# Channel_supply.net
KiCad netlist of a schematic drawn in Altium Designer
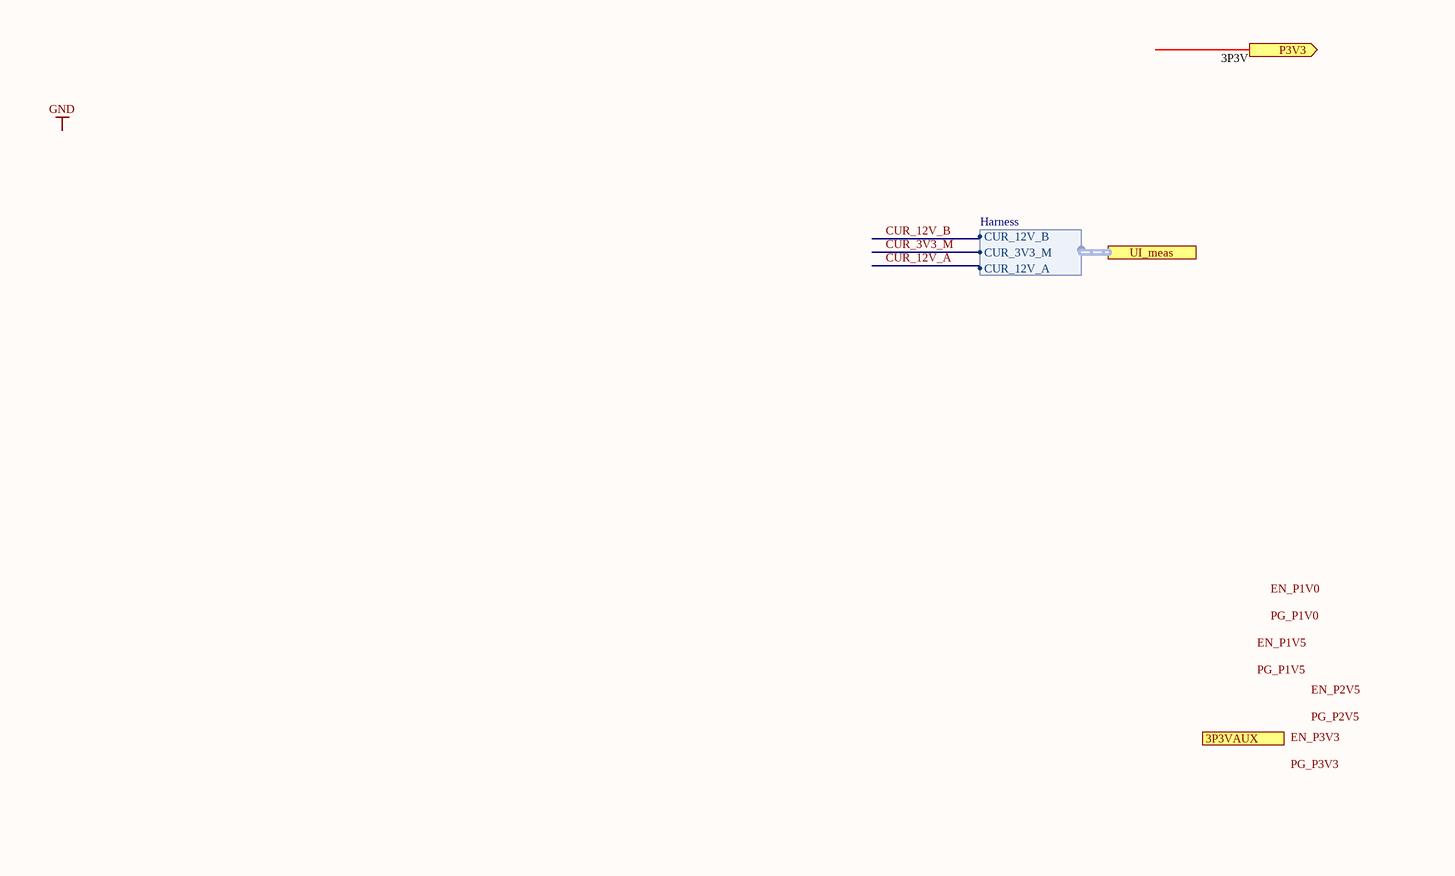
[diagram p0: Channel_supply.SchDoc, left]
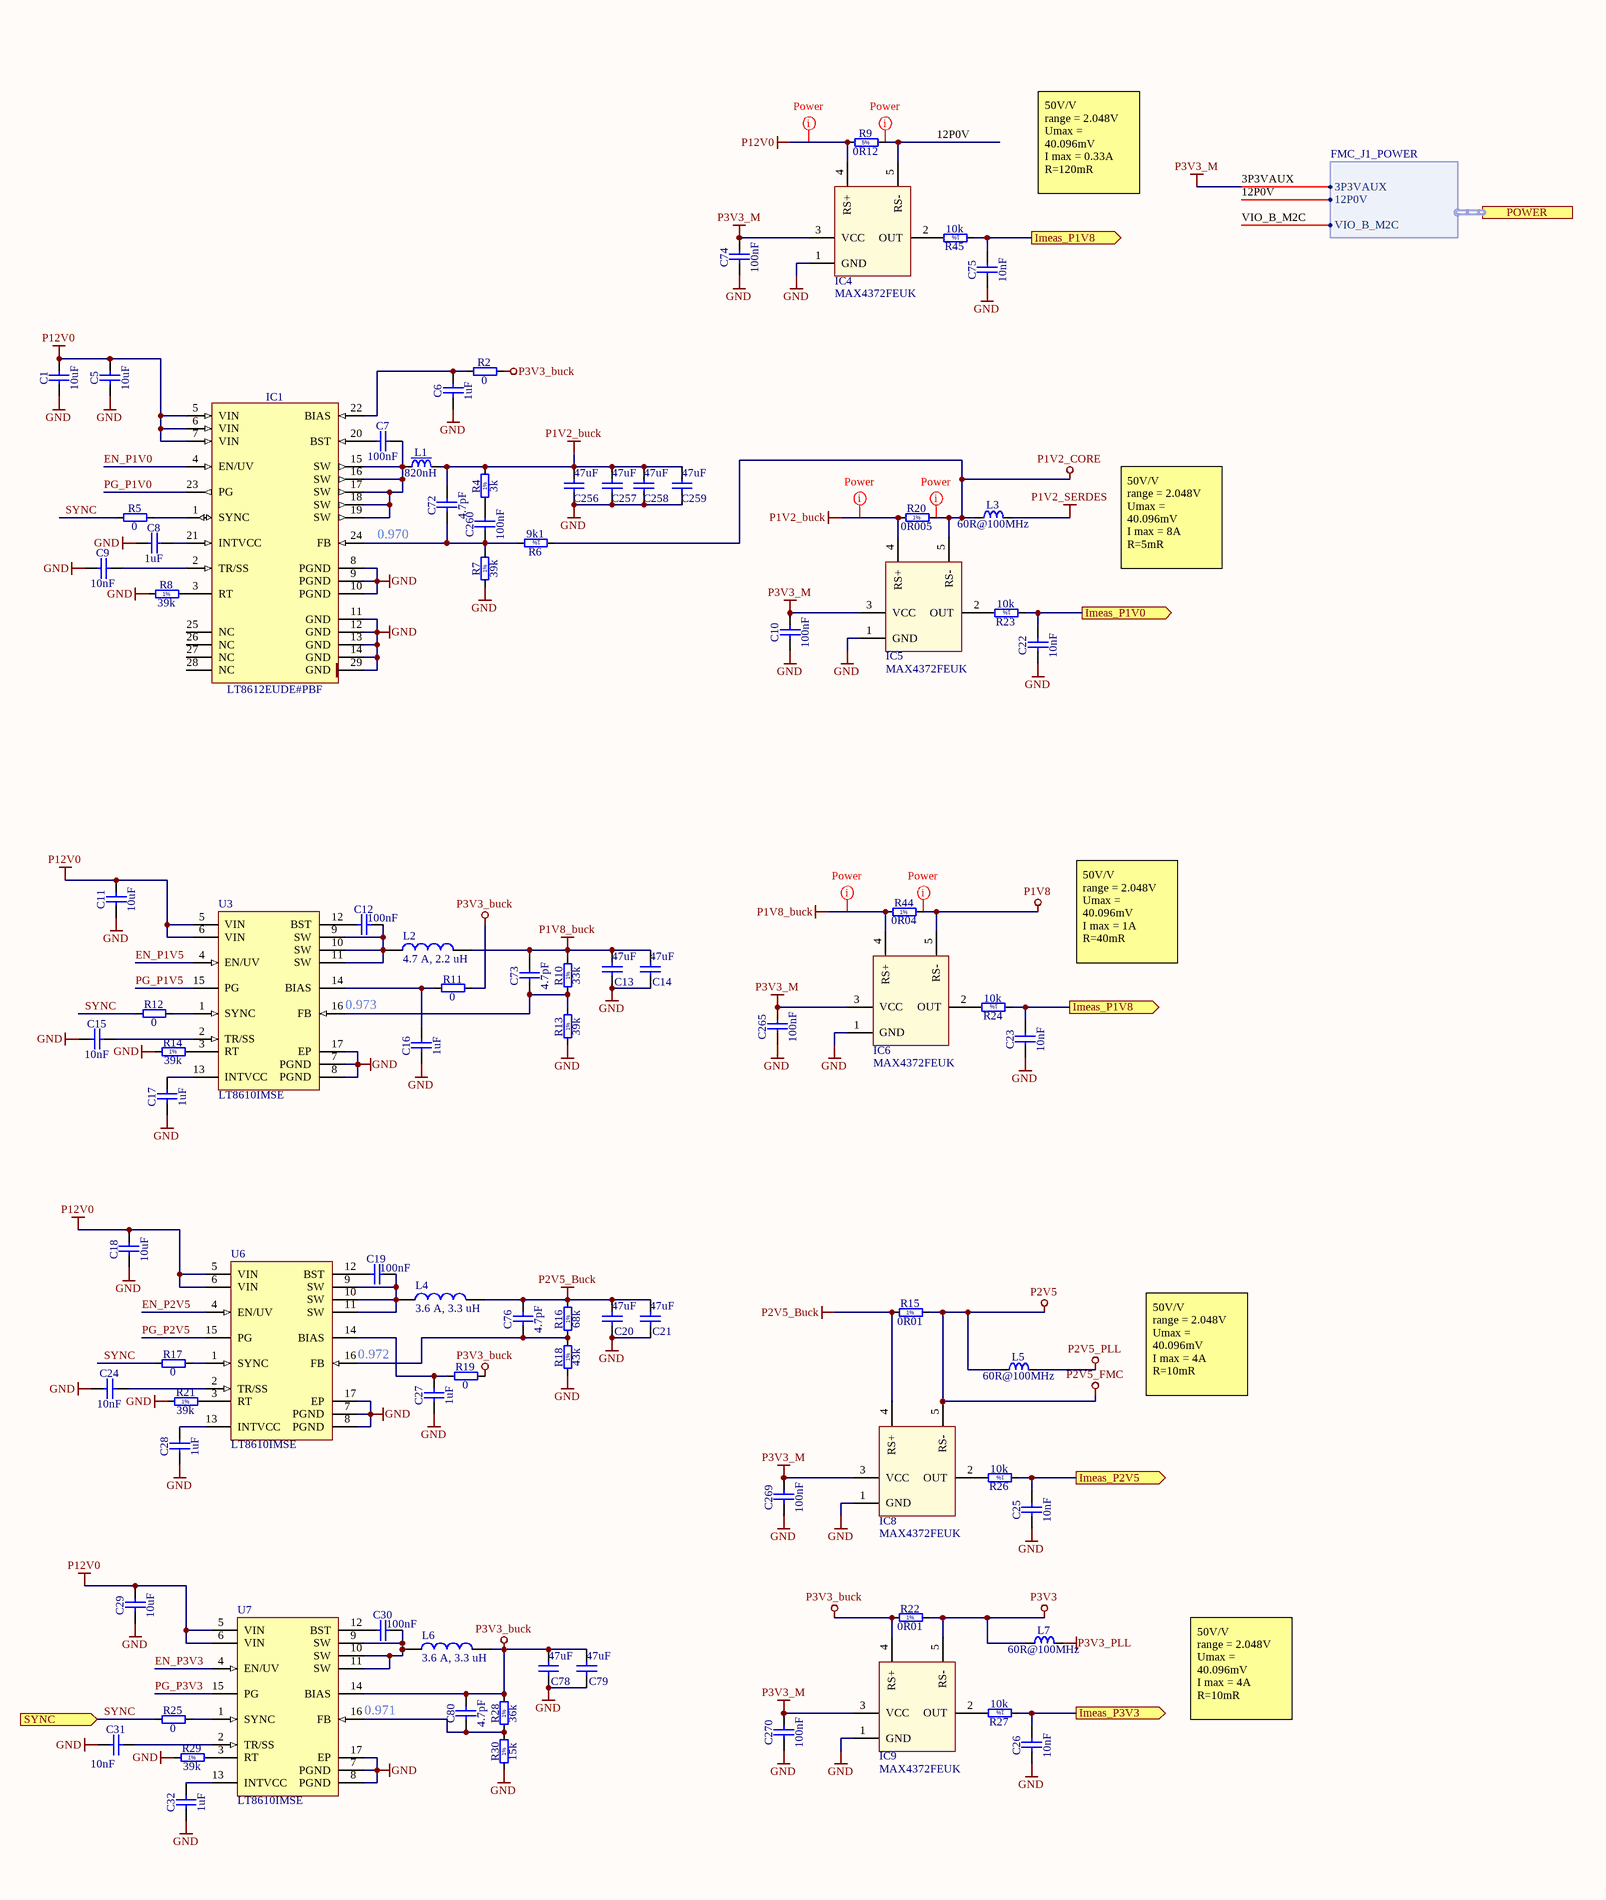
[diagram p1: Channel_supply.SchDoc, right]

(export (version "E")
  (design (tool "Eeschema 10.0.6"))
  (components
    (comp (ref "C1")
      (value "10uF")
      (footprint "CAPC2012X95N")
      (description "Non-polarised capacitor")
      (fields (field (name "PART NUMBER") "CC0805_10UF_25V_10%_X5R") (field (name "VOLTAGE") "25V"))
      (libsource (lib "Capacitors") (part "Capacitor - non polarized"))
    )
    (comp (ref "C5")
      (value "10uF")
      (footprint "CAPC2012X95N")
      (description "Non-polarised capacitor")
      (fields (field (name "PART NUMBER") "CC0805_10UF_25V_10%_X5R") (field (name "VOLTAGE") "25V"))
      (libsource (lib "Capacitors") (part "Capacitor - non polarized"))
    )
    (comp (ref "C6")
      (value "1uF")
      (footprint "CAPC1608X87N")
      (description "Non-polarised capacitor")
      (fields (field (name "PART NUMBER") "CC0603_1UF_25V_10%_X7R") (field (name "VOLTAGE") "25V"))
      (libsource (lib "Capacitors") (part "Capacitor - non polarized"))
    )
    (comp (ref "C7")
      (value "100nF")
      (footprint "CAPC1005X55N")
      (description "Non-polarised capacitor")
      (fields
        (field (name "PART NUMBER") "CC0402_100NF_25V_10%_X7R_YUDEN_TMK105B7104KVHF")
        (field (name "VOLTAGE") "25V")
      )
      (libsource (lib "Capacitors") (part "Capacitor - non polarized"))
    )
    (comp (ref "C8")
      (value "1uF")
      (footprint "CAPC1608X87N")
      (description "Non-polarised capacitor")
      (fields (field (name "PART NUMBER") "CC0603_1UF_25V_10%_X7R") (field (name "VOLTAGE") "25V"))
      (libsource (lib "Capacitors") (part "Capacitor - non polarized"))
    )
    (comp (ref "C9")
      (value "10nF")
      (footprint "CAPC1005X55N")
      (description "Non-polarised capacitor")
      (fields (field (name "PART NUMBER") "CC0402_10NF_25V_10%_X7R") (field (name "VOLTAGE") "25V"))
      (libsource (lib "Capacitors") (part "Capacitor - non polarized"))
    )
    (comp (ref "C10")
      (value "100nF")
      (footprint "CAPC1005X55N")
      (description "Non-polarised capacitor")
      (fields
        (field (name "PART NUMBER") "CC0402_100NF_25V_10%_X7R_YUDEN_TMK105B7104KVHF")
        (field (name "VOLTAGE") "25V")
      )
      (libsource (lib "Capacitors") (part "Capacitor - non polarized"))
    )
    (comp (ref "C11")
      (value "10uF")
      (footprint "CAPC2012X95N")
      (description "Non-polarised capacitor")
      (fields (field (name "PART NUMBER") "CC0805_10UF_25V_10%_X5R") (field (name "VOLTAGE") "25V"))
      (libsource (lib "Capacitors") (part "Capacitor - non polarized"))
    )
    (comp (ref "C12")
      (value "100nF")
      (footprint "CAPC1005X55N")
      (description "Non-polarised capacitor")
      (fields
        (field (name "PART NUMBER") "CC0402_100NF_25V_10%_X7R_YUDEN_TMK105B7104KVHF")
        (field (name "VOLTAGE") "25V")
      )
      (libsource (lib "Capacitors") (part "Capacitor - non polarized"))
    )
    (comp (ref "C13")
      (value "47uF")
      (footprint "CAPC2012X140N")
      (description "Non-polarised capacitor")
      (fields (field (name "PART NUMBER") "CC0805_47UF_6.3V_20%_X5R") (field (name "MANUFACTURER") "GENERIC"))
      (libsource (lib "Capacitors") (part "Capacitor - non polarized"))
    )
    (comp (ref "C14")
      (value "47uF")
      (footprint "CAPC2012X140N")
      (description "Non-polarised capacitor")
      (fields (field (name "PART NUMBER") "CC0805_47UF_6.3V_20%_X5R") (field (name "MANUFACTURER") "GENERIC"))
      (libsource (lib "Capacitors") (part "Capacitor - non polarized"))
    )
    (comp (ref "C15")
      (value "10nF")
      (footprint "CAPC1005X55N")
      (description "Non-polarised capacitor")
      (fields (field (name "PART NUMBER") "CC0402_10NF_25V_10%_X7R") (field (name "VOLTAGE") "25V"))
      (libsource (lib "Capacitors") (part "Capacitor - non polarized"))
    )
    (comp (ref "C16")
      (value "1uF")
      (footprint "CAPC1608X87N")
      (description "Non-polarised capacitor")
      (fields (field (name "PART NUMBER") "CC0603_1UF_25V_10%_X7R") (field (name "VOLTAGE") "25V"))
      (libsource (lib "Capacitors") (part "Capacitor - non polarized"))
    )
    (comp (ref "C17")
      (value "1uF")
      (footprint "CAPC1608X87N")
      (description "Non-polarised capacitor")
      (fields (field (name "PART NUMBER") "CC0603_1UF_25V_10%_X7R") (field (name "VOLTAGE") "25V"))
      (libsource (lib "Capacitors") (part "Capacitor - non polarized"))
    )
    (comp (ref "C18")
      (value "10uF")
      (footprint "CAPC2012X95N")
      (description "Non-polarised capacitor")
      (fields (field (name "PART NUMBER") "CC0805_10UF_25V_10%_X5R") (field (name "VOLTAGE") "25V"))
      (libsource (lib "Capacitors") (part "Capacitor - non polarized"))
    )
    (comp (ref "C19")
      (value "100nF")
      (footprint "CAPC1005X55N")
      (description "Non-polarised capacitor")
      (fields
        (field (name "PART NUMBER") "CC0402_100NF_25V_10%_X7R_YUDEN_TMK105B7104KVHF")
        (field (name "VOLTAGE") "25V")
      )
      (libsource (lib "Capacitors") (part "Capacitor - non polarized"))
    )
    (comp (ref "C20")
      (value "47uF")
      (footprint "CAPC2012X140N")
      (description "Non-polarised capacitor")
      (fields (field (name "PART NUMBER") "CC0805_47UF_6.3V_20%_X5R") (field (name "MANUFACTURER") "GENERIC"))
      (libsource (lib "Capacitors") (part "Capacitor - non polarized"))
    )
    (comp (ref "C21")
      (value "47uF")
      (footprint "CAPC2012X140N")
      (description "Non-polarised capacitor")
      (fields (field (name "PART NUMBER") "CC0805_47UF_6.3V_20%_X5R") (field (name "MANUFACTURER") "GENERIC"))
      (libsource (lib "Capacitors") (part "Capacitor - non polarized"))
    )
    (comp (ref "C22")
      (value "10nF")
      (footprint "CAPC1005X55N")
      (description "Non-polarised capacitor")
      (fields (field (name "PART NUMBER") "CC0402_10NF_50V_10%_X7R") (field (name "VOLTAGE") "50V"))
      (libsource (lib "Capacitors") (part "Capacitor - non polarized"))
    )
    (comp (ref "C23")
      (value "10nF")
      (footprint "CAPC1005X55N")
      (description "Non-polarised capacitor")
      (fields (field (name "PART NUMBER") "CC0402_10NF_50V_10%_X7R") (field (name "VOLTAGE") "50V"))
      (libsource (lib "Capacitors") (part "Capacitor - non polarized"))
    )
    (comp (ref "C24")
      (value "10nF")
      (footprint "CAPC1005X55N")
      (description "Non-polarised capacitor")
      (fields (field (name "PART NUMBER") "CC0402_10NF_25V_10%_X7R") (field (name "VOLTAGE") "25V"))
      (libsource (lib "Capacitors") (part "Capacitor - non polarized"))
    )
    (comp (ref "C25")
      (value "10nF")
      (footprint "CAPC1005X55N")
      (description "Non-polarised capacitor")
      (fields (field (name "PART NUMBER") "CC0402_10NF_50V_10%_X7R") (field (name "VOLTAGE") "50V"))
      (libsource (lib "Capacitors") (part "Capacitor - non polarized"))
    )
    (comp (ref "C26")
      (value "10nF")
      (footprint "CAPC1005X55N")
      (description "Non-polarised capacitor")
      (fields (field (name "PART NUMBER") "CC0402_10NF_50V_10%_X7R") (field (name "VOLTAGE") "50V"))
      (libsource (lib "Capacitors") (part "Capacitor - non polarized"))
    )
    (comp (ref "C27")
      (value "1uF")
      (footprint "CAPC1608X87N")
      (description "Non-polarised capacitor")
      (fields (field (name "PART NUMBER") "CC0603_1UF_25V_10%_X7R") (field (name "VOLTAGE") "25V"))
      (libsource (lib "Capacitors") (part "Capacitor - non polarized"))
    )
    (comp (ref "C28")
      (value "1uF")
      (footprint "CAPC1608X87N")
      (description "Non-polarised capacitor")
      (fields (field (name "PART NUMBER") "CC0603_1UF_25V_10%_X7R") (field (name "VOLTAGE") "25V"))
      (libsource (lib "Capacitors") (part "Capacitor - non polarized"))
    )
    (comp (ref "C29")
      (value "10uF")
      (footprint "CAPC2012X95N")
      (description "Non-polarised capacitor")
      (fields (field (name "PART NUMBER") "CC0805_10UF_25V_10%_X5R") (field (name "VOLTAGE") "25V"))
      (libsource (lib "Capacitors") (part "Capacitor - non polarized"))
    )
    (comp (ref "C30")
      (value "100nF")
      (footprint "CAPC1005X55N")
      (description "Non-polarised capacitor")
      (fields
        (field (name "PART NUMBER") "CC0402_100NF_25V_10%_X7R_YUDEN_TMK105B7104KVHF")
        (field (name "VOLTAGE") "25V")
      )
      (libsource (lib "Capacitors") (part "Capacitor - non polarized"))
    )
    (comp (ref "C31")
      (value "10nF")
      (footprint "CAPC1005X55N")
      (description "Non-polarised capacitor")
      (fields (field (name "PART NUMBER") "CC0402_10NF_25V_10%_X7R") (field (name "VOLTAGE") "25V"))
      (libsource (lib "Capacitors") (part "Capacitor - non polarized"))
    )
    (comp (ref "C32")
      (value "1uF")
      (footprint "CAPC1608X87N")
      (description "Non-polarised capacitor")
      (fields (field (name "PART NUMBER") "CC0603_1UF_25V_10%_X7R") (field (name "VOLTAGE") "25V"))
      (libsource (lib "Capacitors") (part "Capacitor - non polarized"))
    )
    (comp (ref "C72")
      (value "4.7pF")
      (footprint "CAPC1005X55N")
      (description "Non-polarised capacitor")
      (fields (field (name "PART NUMBER") "CC0402_4.7PF_50V_0.25PF_C0G") (field (name "VOLTAGE") "50V"))
      (libsource (lib "Capacitors") (part "Capacitor - non polarized"))
    )
    (comp (ref "C73")
      (value "4.7pF")
      (footprint "CAPC1005X55N")
      (description "Non-polarised capacitor")
      (fields (field (name "PART NUMBER") "CC0402_4.7PF_50V_0.25PF_C0G") (field (name "VOLTAGE") "50V"))
      (libsource (lib "Capacitors") (part "Capacitor - non polarized"))
    )
    (comp (ref "C74")
      (value "100nF")
      (footprint "CAPC1005X55N")
      (description "Non-polarised capacitor")
      (fields
        (field (name "PART NUMBER") "CC0402_100NF_25V_10%_X7R_YUDEN_TMK105B7104KVHF")
        (field (name "VOLTAGE") "25V")
      )
      (libsource (lib "Capacitors") (part "Capacitor - non polarized"))
    )
    (comp (ref "C75")
      (value "10nF")
      (footprint "CAPC1005X55N")
      (description "Non-polarised capacitor")
      (fields (field (name "PART NUMBER") "CC0402_10NF_50V_10%_X7R") (field (name "VOLTAGE") "50V"))
      (libsource (lib "Capacitors") (part "Capacitor - non polarized"))
    )
    (comp (ref "C76")
      (value "4.7pF")
      (footprint "CAPC1005X55N")
      (description "Non-polarised capacitor")
      (fields (field (name "PART NUMBER") "CC0402_4.7PF_50V_0.25PF_C0G") (field (name "VOLTAGE") "50V"))
      (libsource (lib "Capacitors") (part "Capacitor - non polarized"))
    )
    (comp (ref "C78")
      (value "47uF")
      (footprint "CAPC2012X140N")
      (description "Non-polarised capacitor")
      (fields (field (name "PART NUMBER") "CC0805_47UF_6.3V_20%_X5R") (field (name "MANUFACTURER") "GENERIC"))
      (libsource (lib "Capacitors") (part "Capacitor - non polarized"))
    )
    (comp (ref "C79")
      (value "47uF")
      (footprint "CAPC2012X140N")
      (description "Non-polarised capacitor")
      (fields (field (name "PART NUMBER") "CC0805_47UF_6.3V_20%_X5R") (field (name "MANUFACTURER") "GENERIC"))
      (libsource (lib "Capacitors") (part "Capacitor - non polarized"))
    )
    (comp (ref "C80")
      (value "4.7pF")
      (footprint "CAPC1005X55N")
      (description "Non-polarised capacitor")
      (fields (field (name "PART NUMBER") "CC0402_4.7PF_50V_0.25PF_C0G") (field (name "VOLTAGE") "50V"))
      (libsource (lib "Capacitors") (part "Capacitor - non polarized"))
    )
    (comp (ref "C256")
      (value "47uF")
      (footprint "CAPC2012X140N")
      (description "Non-polarised capacitor")
      (fields (field (name "PART NUMBER") "CC0805_47UF_6.3V_20%_X5R") (field (name "MANUFACTURER") "GENERIC"))
      (libsource (lib "Capacitors") (part "Capacitor - non polarized"))
    )
    (comp (ref "C257")
      (value "47uF")
      (footprint "CAPC2012X140N")
      (description "Non-polarised capacitor")
      (fields (field (name "PART NUMBER") "CC0805_47UF_6.3V_20%_X5R") (field (name "MANUFACTURER") "GENERIC"))
      (libsource (lib "Capacitors") (part "Capacitor - non polarized"))
    )
    (comp (ref "C258")
      (value "47uF")
      (footprint "CAPC2012X140N")
      (description "Non-polarised capacitor")
      (fields (field (name "PART NUMBER") "CC0805_47UF_6.3V_20%_X5R") (field (name "MANUFACTURER") "GENERIC"))
      (libsource (lib "Capacitors") (part "Capacitor - non polarized"))
    )
    (comp (ref "C259")
      (value "47uF")
      (footprint "CAPC2012X140N")
      (description "Non-polarised capacitor")
      (fields (field (name "PART NUMBER") "CC0805_47UF_6.3V_20%_X5R") (field (name "MANUFACTURER") "GENERIC"))
      (libsource (lib "Capacitors") (part "Capacitor - non polarized"))
    )
    (comp (ref "C260")
      (value "100nF")
      (footprint "CAPC1005X55N")
      (description "Non-polarised capacitor")
      (fields
        (field (name "PART NUMBER") "CC0402_100NF_25V_10%_X7R_YUDEN_TMK105B7104KVHF")
        (field (name "VOLTAGE") "25V")
      )
      (libsource (lib "Capacitors") (part "Capacitor - non polarized"))
    )
    (comp (ref "C265")
      (value "100nF")
      (footprint "CAPC1005X55N")
      (description "Non-polarised capacitor")
      (fields
        (field (name "PART NUMBER") "CC0402_100NF_25V_10%_X7R_YUDEN_TMK105B7104KVHF")
        (field (name "VOLTAGE") "25V")
      )
      (libsource (lib "Capacitors") (part "Capacitor - non polarized"))
    )
    (comp (ref "C269")
      (value "100nF")
      (footprint "CAPC1005X55N")
      (description "Non-polarised capacitor")
      (fields
        (field (name "PART NUMBER") "CC0402_100NF_25V_10%_X7R_YUDEN_TMK105B7104KVHF")
        (field (name "VOLTAGE") "25V")
      )
      (libsource (lib "Capacitors") (part "Capacitor - non polarized"))
    )
    (comp (ref "C270")
      (value "100nF")
      (footprint "CAPC1005X55N")
      (description "Non-polarised capacitor")
      (fields
        (field (name "PART NUMBER") "CC0402_100NF_25V_10%_X7R_YUDEN_TMK105B7104KVHF")
        (field (name "VOLTAGE") "25V")
      )
      (libsource (lib "Capacitors") (part "Capacitor - non polarized"))
    )
    (comp (ref "IC1")
      (value "LT8612EUDE#PBF")
      (footprint "QFN50P300X600X80-29N-R180X485")
      (description "42V, 6A Synchronous Step-Down Regulator with 3µA Quiescent Current")
      (fields (field (name "MANUFACTURER") "LINEAR TECHNOLOGY"))
      (libsource (lib "ICs And Semiconductors") (part "LT8612"))
    )
    (comp (ref "IC4")
      (value "MAX4372FEUK")
      (footprint "SOT95P270X145-5N")
      (fields (field (name "MANUFACTURER") "Maxim"))
      (libsource (lib "LIBRARY_SCH") (part "PM_MAX4372FEUK"))
    )
    (comp (ref "IC5")
      (value "MAX4372FEUK")
      (footprint "SOT95P270X145-5N")
      (fields (field (name "MANUFACTURER") "Maxim"))
      (libsource (lib "LIBRARY_SCH") (part "PM_MAX4372FEUK"))
    )
    (comp (ref "IC6")
      (value "MAX4372FEUK")
      (footprint "SOT95P270X145-5N")
      (fields (field (name "MANUFACTURER") "Maxim"))
      (libsource (lib "LIBRARY_SCH") (part "PM_MAX4372FEUK"))
    )
    (comp (ref "IC8")
      (value "MAX4372FEUK")
      (footprint "SOT95P270X145-5N")
      (fields (field (name "MANUFACTURER") "Maxim"))
      (libsource (lib "LIBRARY_SCH") (part "PM_MAX4372FEUK"))
    )
    (comp (ref "IC9")
      (value "MAX4372FEUK")
      (footprint "SOT95P270X145-5N")
      (fields (field (name "MANUFACTURER") "Maxim"))
      (libsource (lib "LIBRARY_SCH") (part "PM_MAX4372FEUK"))
    )
    (comp (ref "L1")
      (value "820nH")
      (footprint "INDP4040X21N")
      (description "Inductor With Core")
      (fields (field (name "PART NUMBER") "IND_820NH_COILCRAFT_XEL4020-821MEC") (field (name "POWER") "10A"))
      (libsource (lib "LIBRARY_SCH") (part "L_POWER_XEL4020_820uH_10A"))
    )
    (comp (ref "L2")
      (value "4.7 A, 2.2 uH")
      (footprint "WE-MAIA_4020")
      (description "WE-MAIA SMD Power Inductor, size 4020, 4.7 A, 2.2 uH")
      (fields (field (name "PART NUMBER") "78438356022"))
      (libsource (lib "ALTIUM-WE-MAIA-rev17b") (part "78438356022"))
    )
    (comp (ref "L3")
      (value "60R@100MHz")
      (footprint "INDC4516X180N")
      (description "Inductor")
      (fields (field (name "PART NUMBER") "IND1806_MURATA_BLM41PG600SN1L") (field (name "POWER") "6A"))
      (libsource (lib "Inductors & Transformers") (part "Inductor"))
    )
    (comp (ref "L4")
      (value "3.6 A, 3.3 uH")
      (footprint "WE-MAIA_4020")
      (description "WE-MAIA SMD Power Inductor, size 4020, 3.6 A, 3.3 uH")
      (fields (field (name "PART NUMBER") "78438356033"))
      (libsource (lib "ALTIUM-WE-MAIA-rev17b") (part "78438356033"))
    )
    (comp (ref "L5")
      (value "60R@100MHz")
      (footprint "INDC4516X180N")
      (description "Inductor")
      (fields (field (name "PART NUMBER") "IND1806_MURATA_BLM41PG600SN1L") (field (name "POWER") "6A"))
      (libsource (lib "Inductors & Transformers") (part "Inductor"))
    )
    (comp (ref "L6")
      (value "3.6 A, 3.3 uH")
      (footprint "WE-MAIA_4020")
      (description "WE-MAIA SMD Power Inductor, size 4020, 3.6 A, 3.3 uH")
      (fields (field (name "PART NUMBER") "78438356033"))
      (libsource (lib "ALTIUM-WE-MAIA-rev17b") (part "78438356033"))
    )
    (comp (ref "L7")
      (value "60R@100MHz")
      (footprint "INDC4516X180N")
      (description "Inductor")
      (fields (field (name "PART NUMBER") "IND1806_MURATA_BLM41PG600SN1L") (field (name "POWER") "6A"))
      (libsource (lib "Inductors & Transformers") (part "Inductor"))
    )
    (comp (ref "R2")
      (value "0")
      (footprint "RESC1005X40N")
      (description "Resistor")
      (fields (field (name "PART NUMBER") "R0402_0R_JUMPER") (field (name "MANUFACTURER") "GENERIC"))
      (libsource (lib "Resistors") (part "Resistor"))
    )
    (comp (ref "R4")
      (value "3k")
      (footprint "RESC1005X40N")
      (description "Resistor - 1%")
      (fields (field (name "PART NUMBER") "R0402_3K_1%_0.0625W_100PPM") (field (name "POWER") "0.0625W"))
      (libsource (lib "Resistors") (part "Resistor - 1%"))
    )
    (comp (ref "R5")
      (value "0")
      (footprint "RESC1005X40N")
      (description "Resistor")
      (fields (field (name "PART NUMBER") "R0402_0R_JUMPER") (field (name "MANUFACTURER") "GENERIC"))
      (libsource (lib "Resistors") (part "Resistor"))
    )
    (comp (ref "R6")
      (value "9k1")
      (footprint "RESC1005X40N")
      (description "Resistor - 1%")
      (fields (field (name "PART NUMBER") "R0402_9K1_1%_0.0625W_100PPM") (field (name "POWER") "0.0625W"))
      (libsource (lib "Resistors") (part "Resistor - 1%"))
    )
    (comp (ref "R7")
      (value "39k")
      (footprint "RESC1005X40N")
      (description "Resistor - 1%")
      (fields (field (name "PART NUMBER") "R0402_39K_1%_0.0625W_100PPM") (field (name "POWER") "0.0625W"))
      (libsource (lib "Resistors") (part "Resistor - 1%"))
    )
    (comp (ref "R8")
      (value "39k")
      (footprint "RESC1005X40N")
      (description "Resistor - 1%")
      (fields (field (name "PART NUMBER") "R0402_39K_1%_0.0625W_100PPM") (field (name "POWER") "0.0625W"))
      (libsource (lib "Resistors") (part "Resistor - 1%"))
    )
    (comp (ref "R9")
      (value "0R12")
      (footprint "RESC2012X70N")
      (description "Resistor - 5%")
      (fields
        (field (name "PART NUMBER") "R0805_0R12_5%_0.25W_250PPM_PANASONIC_ERJ")
        (field (name "POWER") "0.25W")
      )
      (libsource (lib "Resistors") (part "Resistor - 5%"))
    )
    (comp (ref "R10")
      (value "33k")
      (footprint "RESC1005X40N")
      (description "Resistor - 1%")
      (fields (field (name "PART NUMBER") "R0402_33K_1%_0.0625W_100PPM") (field (name "POWER") "0.0625W"))
      (libsource (lib "Resistors") (part "Resistor - 1%"))
    )
    (comp (ref "R11")
      (value "0")
      (footprint "RESC1005X40N")
      (description "Resistor")
      (fields (field (name "PART NUMBER") "R0402_0R_JUMPER") (field (name "MANUFACTURER") "GENERIC"))
      (libsource (lib "Resistors") (part "Resistor"))
    )
    (comp (ref "R12")
      (value "0")
      (footprint "RESC1005X40N")
      (description "Resistor")
      (fields (field (name "PART NUMBER") "R0402_0R_JUMPER") (field (name "MANUFACTURER") "GENERIC"))
      (libsource (lib "Resistors") (part "Resistor"))
    )
    (comp (ref "R13")
      (value "39k")
      (footprint "RESC1005X40N")
      (description "Resistor - 1%")
      (fields (field (name "PART NUMBER") "R0402_39K_1%_0.0625W_100PPM") (field (name "POWER") "0.0625W"))
      (libsource (lib "Resistors") (part "Resistor - 1%"))
    )
    (comp (ref "R14")
      (value "39k")
      (footprint "RESC1005X40N")
      (description "Resistor - 1%")
      (fields (field (name "PART NUMBER") "R0402_39K_1%_0.0625W_100PPM") (field (name "POWER") "0.0625W"))
      (libsource (lib "Resistors") (part "Resistor - 1%"))
    )
    (comp (ref "R15")
      (value "0R01")
      (footprint "RESC3216X80N")
      (description "Resistor - 1%")
      (fields (field (name "PART NUMBER") "R1206_0R01_1%_1W_100PPM_TT_LRMAM1206") (field (name "POWER") "1W"))
      (libsource (lib "Resistors") (part "Resistor - 1%"))
    )
    (comp (ref "R16")
      (value "68k")
      (footprint "RESC1005X40N")
      (description "Resistor - 1%")
      (fields (field (name "PART NUMBER") "R0402_68K_1%_0.0625W_100PPM") (field (name "POWER") "0.0625W"))
      (libsource (lib "Resistors") (part "Resistor - 1%"))
    )
    (comp (ref "R17")
      (value "0")
      (footprint "RESC1005X40N")
      (description "Resistor")
      (fields (field (name "PART NUMBER") "R0402_0R_JUMPER") (field (name "MANUFACTURER") "GENERIC"))
      (libsource (lib "Resistors") (part "Resistor"))
    )
    (comp (ref "R18")
      (value "43k")
      (footprint "RESC1005X40N")
      (description "Resistor - 1%")
      (fields (field (name "PART NUMBER") "R0402_43K_1%_0.0625W_100PPM") (field (name "POWER") "0.0625W"))
      (libsource (lib "Resistors") (part "Resistor - 1%"))
    )
    (comp (ref "R19")
      (value "0")
      (footprint "RESC1005X40N")
      (description "Resistor")
      (fields (field (name "PART NUMBER") "R0402_0R_JUMPER") (field (name "MANUFACTURER") "GENERIC"))
      (libsource (lib "Resistors") (part "Resistor"))
    )
    (comp (ref "R20")
      (value "0R005")
      (footprint "RESC3216X80N")
      (description "Resistor - 1%")
      (fields
        (field (name "PART NUMBER") "R1206_0R005_1%_1W_100PPM_TT_LRMAM1206")
        (field (name "POWER") "1W")
      )
      (libsource (lib "Resistors") (part "Resistor - 1%"))
    )
    (comp (ref "R21")
      (value "39k")
      (footprint "RESC1005X40N")
      (description "Resistor - 1%")
      (fields (field (name "PART NUMBER") "R0402_39K_1%_0.0625W_100PPM") (field (name "POWER") "0.0625W"))
      (libsource (lib "Resistors") (part "Resistor - 1%"))
    )
    (comp (ref "R22")
      (value "0R01")
      (footprint "RESC3216X80N")
      (description "Resistor - 1%")
      (fields (field (name "PART NUMBER") "R1206_0R01_1%_1W_100PPM_TT_LRMAM1206") (field (name "POWER") "1W"))
      (libsource (lib "Resistors") (part "Resistor - 1%"))
    )
    (comp (ref "R23")
      (value "10k")
      (footprint "RESC1005X40N")
      (description "Resistor - 1%")
      (fields (field (name "PART NUMBER") "R0402_10K_1%_0.0625W_100PPM") (field (name "POWER") "0.0625W"))
      (libsource (lib "Resistors") (part "Resistor - 1%"))
    )
    (comp (ref "R24")
      (value "10k")
      (footprint "RESC1005X40N")
      (description "Resistor - 1%")
      (fields (field (name "PART NUMBER") "R0402_10K_1%_0.0625W_100PPM") (field (name "POWER") "0.0625W"))
      (libsource (lib "Resistors") (part "Resistor - 1%"))
    )
    (comp (ref "R25")
      (value "0")
      (footprint "RESC1005X40N")
      (description "Resistor")
      (fields (field (name "PART NUMBER") "R0402_0R_JUMPER") (field (name "MANUFACTURER") "GENERIC"))
      (libsource (lib "Resistors") (part "Resistor"))
    )
    (comp (ref "R26")
      (value "10k")
      (footprint "RESC1005X40N")
      (description "Resistor - 1%")
      (fields (field (name "PART NUMBER") "R0402_10K_1%_0.0625W_100PPM") (field (name "POWER") "0.0625W"))
      (libsource (lib "Resistors") (part "Resistor - 1%"))
    )
    (comp (ref "R27")
      (value "10k")
      (footprint "RESC1005X40N")
      (description "Resistor - 1%")
      (fields (field (name "PART NUMBER") "R0402_10K_1%_0.0625W_100PPM") (field (name "POWER") "0.0625W"))
      (libsource (lib "Resistors") (part "Resistor - 1%"))
    )
    (comp (ref "R28")
      (value "36k")
      (footprint "RESC1005X40N")
      (description "Resistor - 1%")
      (fields (field (name "PART NUMBER") "R0402_36K_1%_0.0625W_100PPM") (field (name "POWER") "0.0625W"))
      (libsource (lib "Resistors") (part "Resistor - 1%"))
    )
    (comp (ref "R29")
      (value "39k")
      (footprint "RESC1005X40N")
      (description "Resistor - 1%")
      (fields (field (name "PART NUMBER") "R0402_39K_1%_0.0625W_100PPM") (field (name "POWER") "0.0625W"))
      (libsource (lib "Resistors") (part "Resistor - 1%"))
    )
    (comp (ref "R30")
      (value "15k")
      (footprint "RESC1005X40N")
      (description "Resistor - 1%")
      (fields (field (name "PART NUMBER") "R0402_15K_1%_0.0625W_100PPM") (field (name "POWER") "0.0625W"))
      (libsource (lib "Resistors") (part "Resistor - 1%"))
    )
    (comp (ref "R44")
      (value "0R04")
      (footprint "RESC3216X89N")
      (description "Resistor - 1%")
      (fields
        (field (name "PART NUMBER") "R1206_0R04_1%_0.5W_100PPM_VISHAY_WSL")
        (field (name "POWER") "0.5W")
      )
      (libsource (lib "Resistors") (part "Resistor - 1%"))
    )
    (comp (ref "R45")
      (value "10k")
      (footprint "RESC1005X40N")
      (description "Resistor - 1%")
      (fields (field (name "PART NUMBER") "R0402_10K_1%_0.0625W_100PPM") (field (name "POWER") "0.0625W"))
      (libsource (lib "Resistors") (part "Resistor - 1%"))
    )
    (comp (ref "U3")
      (value "LT8610IMSE")
      (footprint "LT-MSE-16-EDP_L")
      (fields (field (name "MANUFACTURER") "Linear Technology"))
      (libsource (lib "Altium Content Vault") (part "LT-LT8610-MSE-16"))
    )
    (comp (ref "U6")
      (value "LT8610IMSE")
      (footprint "LT-MSE-16-EDP_L")
      (fields (field (name "MANUFACTURER") "Linear Technology"))
      (libsource (lib "Altium Content Vault") (part "LT-LT8610-MSE-16"))
    )
    (comp (ref "U7")
      (value "LT8610IMSE")
      (footprint "LT-MSE-16-EDP_L")
      (fields (field (name "MANUFACTURER") "Linear Technology"))
      (libsource (lib "Altium Content Vault") (part "LT-LT8610-MSE-16"))
    )
  )
  (nets
    (net (code "3") (name "/12P0V") (class "Default")
      (node (ref "IC4") (pin "5") (pinfunction "RS-_5") (pintype "passive"))
      (node (ref "R9") (pin "2") (pinfunction "2_2") (pintype "passive"))
    )
    (net (code "7") (name "/EN_P1V0") (class "Default")
      (node (ref "IC1") (pin "4") (pinfunction "EN/UV_4") (pintype "input"))
    )
    (net (code "8") (name "/EN_P1V5") (class "Default")
      (node (ref "U3") (pin "4") (pinfunction "EN/UV_4") (pintype "input"))
    )
    (net (code "9") (name "/EN_P2V5") (class "Default")
      (node (ref "U6") (pin "4") (pinfunction "EN/UV_4") (pintype "input"))
    )
    (net (code "10") (name "/EN_P3V3") (class "Default")
      (node (ref "U7") (pin "4") (pinfunction "EN/UV_4") (pintype "input"))
    )
    (net (code "11") (name "/Imeas_P1V0") (class "Default")
      (node (ref "C22") (pin "2") (pinfunction "2_2") (pintype "passive"))
      (node (ref "R23") (pin "1") (pinfunction "1_1") (pintype "passive"))
    )
    (net (code "12") (name "/Imeas_P1V8") (class "Default")
      (node (ref "C23") (pin "2") (pinfunction "2_2") (pintype "passive"))
      (node (ref "C75") (pin "2") (pinfunction "2_2") (pintype "passive"))
      (node (ref "R24") (pin "1") (pinfunction "1_1") (pintype "passive"))
      (node (ref "R45") (pin "1") (pinfunction "1_1") (pintype "passive"))
    )
    (net (code "13") (name "/Imeas_P2V5") (class "Default")
      (node (ref "C25") (pin "2") (pinfunction "2_2") (pintype "passive"))
      (node (ref "R26") (pin "1") (pinfunction "1_1") (pintype "passive"))
    )
    (net (code "14") (name "/Imeas_P3V3") (class "Default")
      (node (ref "C26") (pin "2") (pinfunction "2_2") (pintype "passive"))
      (node (ref "R27") (pin "1") (pinfunction "1_1") (pintype "passive"))
    )
    (net (code "15") (name "/PG_P1V0") (class "Default")
      (node (ref "IC1") (pin "23") (pinfunction "PG_23") (pintype "output"))
    )
    (net (code "16") (name "/PG_P1V5") (class "Default")
      (node (ref "U3") (pin "15") (pinfunction "PG_15") (pintype "tri_state"))
    )
    (net (code "17") (name "/PG_P2V5") (class "Default")
      (node (ref "U6") (pin "15") (pinfunction "PG_15") (pintype "tri_state"))
    )
    (net (code "18") (name "/PG_P3V3") (class "Default")
      (node (ref "U7") (pin "15") (pinfunction "PG_15") (pintype "tri_state"))
    )
    (net (code "19") (name "/SYNC") (class "Default")
      (node (ref "R12") (pin "1") (pinfunction "1_1") (pintype "passive"))
      (node (ref "R17") (pin "1") (pinfunction "1_1") (pintype "passive"))
      (node (ref "R25") (pin "1") (pinfunction "1_1") (pintype "passive"))
      (node (ref "R5") (pin "1") (pinfunction "1_1") (pintype "passive"))
    )
    (net (code "23") (name "GND") (class "Default")
      (node (ref "C1") (pin "1") (pinfunction "1_1") (pintype "passive"))
      (node (ref "C10") (pin "1") (pinfunction "1_1") (pintype "passive"))
      (node (ref "C11") (pin "1") (pinfunction "1_1") (pintype "passive"))
      (node (ref "C13") (pin "1") (pinfunction "1_1") (pintype "passive"))
      (node (ref "C14") (pin "1") (pinfunction "1_1") (pintype "passive"))
      (node (ref "C15") (pin "1") (pinfunction "1_1") (pintype "passive"))
      (node (ref "C16") (pin "1") (pinfunction "1_1") (pintype "passive"))
      (node (ref "C17") (pin "1") (pinfunction "1_1") (pintype "passive"))
      (node (ref "C18") (pin "1") (pinfunction "1_1") (pintype "passive"))
      (node (ref "C20") (pin "1") (pinfunction "1_1") (pintype "passive"))
      (node (ref "C21") (pin "1") (pinfunction "1_1") (pintype "passive"))
      (node (ref "C22") (pin "1") (pinfunction "1_1") (pintype "passive"))
      (node (ref "C23") (pin "1") (pinfunction "1_1") (pintype "passive"))
      (node (ref "C24") (pin "1") (pinfunction "1_1") (pintype "passive"))
      (node (ref "C25") (pin "1") (pinfunction "1_1") (pintype "passive"))
      (node (ref "C256") (pin "1") (pinfunction "1_1") (pintype "passive"))
      (node (ref "C257") (pin "1") (pinfunction "1_1") (pintype "passive"))
      (node (ref "C258") (pin "1") (pinfunction "1_1") (pintype "passive"))
      (node (ref "C259") (pin "1") (pinfunction "1_1") (pintype "passive"))
      (node (ref "C26") (pin "1") (pinfunction "1_1") (pintype "passive"))
      (node (ref "C265") (pin "1") (pinfunction "1_1") (pintype "passive"))
      (node (ref "C269") (pin "1") (pinfunction "1_1") (pintype "passive"))
      (node (ref "C27") (pin "1") (pinfunction "1_1") (pintype "passive"))
      (node (ref "C270") (pin "1") (pinfunction "1_1") (pintype "passive"))
      (node (ref "C28") (pin "1") (pinfunction "1_1") (pintype "passive"))
      (node (ref "C29") (pin "1") (pinfunction "1_1") (pintype "passive"))
      (node (ref "C31") (pin "1") (pinfunction "1_1") (pintype "passive"))
      (node (ref "C32") (pin "1") (pinfunction "1_1") (pintype "passive"))
      (node (ref "C5") (pin "1") (pinfunction "1_1") (pintype "passive"))
      (node (ref "C6") (pin "1") (pinfunction "1_1") (pintype "passive"))
      (node (ref "C74") (pin "1") (pinfunction "1_1") (pintype "passive"))
      (node (ref "C75") (pin "1") (pinfunction "1_1") (pintype "passive"))
      (node (ref "C78") (pin "1") (pinfunction "1_1") (pintype "passive"))
      (node (ref "C79") (pin "1") (pinfunction "1_1") (pintype "passive"))
      (node (ref "C8") (pin "1") (pinfunction "1_1") (pintype "passive"))
      (node (ref "C9") (pin "1") (pinfunction "1_1") (pintype "passive"))
      (node (ref "IC1") (pin "10") (pinfunction "PGND_10") (pintype "power_in"))
      (node (ref "IC1") (pin "11") (pinfunction "GND_11") (pintype "power_in"))
      (node (ref "IC1") (pin "12") (pinfunction "GND_12") (pintype "power_in"))
      (node (ref "IC1") (pin "13") (pinfunction "GND_13") (pintype "power_in"))
      (node (ref "IC1") (pin "14") (pinfunction "GND_14") (pintype "power_in"))
      (node (ref "IC1") (pin "29") (pinfunction "GND_29") (pintype "power_in"))
      (node (ref "IC1") (pin "8") (pinfunction "PGND_8") (pintype "power_in"))
      (node (ref "IC1") (pin "9") (pinfunction "PGND_9") (pintype "power_in"))
      (node (ref "IC4") (pin "1") (pinfunction "GND_1") (pintype "passive"))
      (node (ref "IC5") (pin "1") (pinfunction "GND_1") (pintype "passive"))
      (node (ref "IC6") (pin "1") (pinfunction "GND_1") (pintype "passive"))
      (node (ref "IC8") (pin "1") (pinfunction "GND_1") (pintype "passive"))
      (node (ref "IC9") (pin "1") (pinfunction "GND_1") (pintype "passive"))
      (node (ref "R13") (pin "1") (pinfunction "1_1") (pintype "passive"))
      (node (ref "R14") (pin "1") (pinfunction "1_1") (pintype "passive"))
      (node (ref "R18") (pin "1") (pinfunction "1_1") (pintype "passive"))
      (node (ref "R21") (pin "1") (pinfunction "1_1") (pintype "passive"))
      (node (ref "R29") (pin "1") (pinfunction "1_1") (pintype "passive"))
      (node (ref "R30") (pin "1") (pinfunction "1_1") (pintype "passive"))
      (node (ref "R7") (pin "1") (pinfunction "1_1") (pintype "passive"))
      (node (ref "R8") (pin "1") (pinfunction "1_1") (pintype "passive"))
      (node (ref "U3") (pin "17") (pinfunction "EP_17") (pintype "power_in"))
      (node (ref "U3") (pin "7") (pinfunction "PGND_7") (pintype "power_in"))
      (node (ref "U3") (pin "8") (pinfunction "PGND_8") (pintype "power_in"))
      (node (ref "U6") (pin "17") (pinfunction "EP_17") (pintype "power_in"))
      (node (ref "U6") (pin "7") (pinfunction "PGND_7") (pintype "power_in"))
      (node (ref "U6") (pin "8") (pinfunction "PGND_8") (pintype "power_in"))
      (node (ref "U7") (pin "17") (pinfunction "EP_17") (pintype "power_in"))
      (node (ref "U7") (pin "7") (pinfunction "PGND_7") (pintype "power_in"))
      (node (ref "U7") (pin "8") (pinfunction "PGND_8") (pintype "power_in"))
    )
    (net (code "24") (name "Net-(C7-Pad2)") (class "Default")
      (node (ref "C7") (pin "2") (pinfunction "2_2") (pintype "passive"))
      (node (ref "IC1") (pin "15") (pinfunction "SW_15") (pintype "output"))
      (node (ref "IC1") (pin "16") (pinfunction "SW_16") (pintype "output"))
      (node (ref "IC1") (pin "17") (pinfunction "SW_17") (pintype "output"))
      (node (ref "IC1") (pin "18") (pinfunction "SW_18") (pintype "output"))
      (node (ref "IC1") (pin "19") (pinfunction "SW_19") (pintype "output"))
      (node (ref "L1") (pin "1") (pinfunction "1_1") (pintype "passive"))
    )
    (net (code "25") (name "Net-(C12-Pad2)") (class "Default")
      (node (ref "C12") (pin "2") (pinfunction "2_2") (pintype "passive"))
      (node (ref "L2") (pin "1") (pinfunction "1_1") (pintype "passive"))
      (node (ref "U3") (pin "10") (pinfunction "SW_10") (pintype "power_in"))
      (node (ref "U3") (pin "11") (pinfunction "SW_11") (pintype "power_in"))
      (node (ref "U3") (pin "9") (pinfunction "SW_9") (pintype "power_in"))
    )
    (net (code "26") (name "Net-(C19-Pad2)") (class "Default")
      (node (ref "C19") (pin "2") (pinfunction "2_2") (pintype "passive"))
      (node (ref "L4") (pin "1") (pinfunction "1_1") (pintype "passive"))
      (node (ref "U6") (pin "10") (pinfunction "SW_10") (pintype "power_in"))
      (node (ref "U6") (pin "11") (pinfunction "SW_11") (pintype "power_in"))
      (node (ref "U6") (pin "9") (pinfunction "SW_9") (pintype "power_in"))
    )
    (net (code "27") (name "Net-(C30-Pad2)") (class "Default")
      (node (ref "C30") (pin "2") (pinfunction "2_2") (pintype "passive"))
      (node (ref "L6") (pin "1") (pinfunction "1_1") (pintype "passive"))
      (node (ref "U7") (pin "10") (pinfunction "SW_10") (pintype "power_in"))
      (node (ref "U7") (pin "11") (pinfunction "SW_11") (pintype "power_in"))
      (node (ref "U7") (pin "9") (pinfunction "SW_9") (pintype "power_in"))
    )
    (net (code "28") (name "Net-(C260-Pad2)") (class "Default")
      (node (ref "C260") (pin "2") (pinfunction "2_2") (pintype "passive"))
      (node (ref "R4") (pin "1") (pinfunction "1_1") (pintype "passive"))
    )
    (net (code "29") (name "Net-(IC1-BIAS)") (class "Default")
      (node (ref "C6") (pin "2") (pinfunction "2_2") (pintype "passive"))
      (node (ref "IC1") (pin "22") (pinfunction "BIAS_22") (pintype "input"))
      (node (ref "R2") (pin "1") (pinfunction "1_1") (pintype "passive"))
    )
    (net (code "30") (name "Net-(IC1-BST)") (class "Default")
      (node (ref "C7") (pin "1") (pinfunction "1_1") (pintype "passive"))
      (node (ref "IC1") (pin "20") (pinfunction "BST_20") (pintype "input"))
    )
    (net (code "31") (name "Net-(IC1-FB)") (class "Default")
      (node (ref "C260") (pin "1") (pinfunction "1_1") (pintype "passive"))
      (node (ref "C72") (pin "1") (pinfunction "1_1") (pintype "passive"))
      (node (ref "IC1") (pin "24") (pinfunction "FB_24") (pintype "input"))
      (node (ref "R6") (pin "2") (pinfunction "2_2") (pintype "passive"))
      (node (ref "R7") (pin "2") (pinfunction "2_2") (pintype "passive"))
    )
    (net (code "32") (name "Net-(IC1-INTVCC)") (class "Default")
      (node (ref "C8") (pin "2") (pinfunction "2_2") (pintype "passive"))
      (node (ref "IC1") (pin "21") (pinfunction "INTVCC_21") (pintype "input"))
    )
    (net (code "33") (name "Net-(IC1-RT)") (class "Default")
      (node (ref "IC1") (pin "3") (pinfunction "RT_3") (pintype "passive"))
      (node (ref "R8") (pin "2") (pinfunction "2_2") (pintype "passive"))
    )
    (net (code "34") (name "Net-(IC1-SYNC)") (class "Default")
      (node (ref "IC1") (pin "1") (pinfunction "SYNC_1") (pintype "bidirectional"))
      (node (ref "R5") (pin "2") (pinfunction "2_2") (pintype "passive"))
    )
    (net (code "35") (name "Net-(IC1-TR{slash}SS)") (class "Default")
      (node (ref "C9") (pin "2") (pinfunction "2_2") (pintype "passive"))
      (node (ref "IC1") (pin "2") (pinfunction "TR/SS_2") (pintype "input"))
    )
    (net (code "36") (name "Net-(IC4-OUT)") (class "Default")
      (node (ref "IC4") (pin "2") (pinfunction "OUT_2") (pintype "passive"))
      (node (ref "R45") (pin "2") (pinfunction "2_2") (pintype "passive"))
    )
    (net (code "37") (name "Net-(IC5-OUT)") (class "Default")
      (node (ref "IC5") (pin "2") (pinfunction "OUT_2") (pintype "passive"))
      (node (ref "R23") (pin "2") (pinfunction "2_2") (pintype "passive"))
    )
    (net (code "38") (name "Net-(IC6-OUT)") (class "Default")
      (node (ref "IC6") (pin "2") (pinfunction "OUT_2") (pintype "passive"))
      (node (ref "R24") (pin "2") (pinfunction "2_2") (pintype "passive"))
    )
    (net (code "39") (name "Net-(IC8-OUT)") (class "Default")
      (node (ref "IC8") (pin "2") (pinfunction "OUT_2") (pintype "passive"))
      (node (ref "R26") (pin "2") (pinfunction "2_2") (pintype "passive"))
    )
    (net (code "40") (name "Net-(IC9-OUT)") (class "Default")
      (node (ref "IC9") (pin "2") (pinfunction "OUT_2") (pintype "passive"))
      (node (ref "R27") (pin "2") (pinfunction "2_2") (pintype "passive"))
    )
    (net (code "41") (name "Net-(U3-BIAS)") (class "Default")
      (node (ref "C16") (pin "2") (pinfunction "2_2") (pintype "passive"))
      (node (ref "R11") (pin "1") (pinfunction "1_1") (pintype "passive"))
      (node (ref "U3") (pin "14") (pinfunction "BIAS_14") (pintype "power_in"))
    )
    (net (code "42") (name "Net-(U3-BST)") (class "Default")
      (node (ref "C12") (pin "1") (pinfunction "1_1") (pintype "passive"))
      (node (ref "U3") (pin "12") (pinfunction "BST_12") (pintype "passive"))
    )
    (net (code "43") (name "Net-(U3-FB)") (class "Default")
      (node (ref "C73") (pin "1") (pinfunction "1_1") (pintype "passive"))
      (node (ref "R10") (pin "1") (pinfunction "1_1") (pintype "passive"))
      (node (ref "R13") (pin "2") (pinfunction "2_2") (pintype "passive"))
      (node (ref "U3") (pin "16") (pinfunction "FB_16") (pintype "input"))
    )
    (net (code "44") (name "Net-(U3-INTVCC)") (class "Default")
      (node (ref "C17") (pin "2") (pinfunction "2_2") (pintype "passive"))
      (node (ref "U3") (pin "13") (pinfunction "INTVCC_13") (pintype "power_in"))
    )
    (net (code "45") (name "Net-(U3-RT)") (class "Default")
      (node (ref "R14") (pin "2") (pinfunction "2_2") (pintype "passive"))
      (node (ref "U3") (pin "3") (pinfunction "RT_3") (pintype "passive"))
    )
    (net (code "46") (name "Net-(U3-SYNC)") (class "Default")
      (node (ref "R12") (pin "2") (pinfunction "2_2") (pintype "passive"))
      (node (ref "U3") (pin "1") (pinfunction "SYNC_1") (pintype "input"))
    )
    (net (code "47") (name "Net-(U3-TR{slash}SS)") (class "Default")
      (node (ref "C15") (pin "2") (pinfunction "2_2") (pintype "passive"))
      (node (ref "U3") (pin "2") (pinfunction "TR/SS_2") (pintype "input"))
    )
    (net (code "48") (name "Net-(U6-BIAS)") (class "Default")
      (node (ref "C27") (pin "2") (pinfunction "2_2") (pintype "passive"))
      (node (ref "R19") (pin "1") (pinfunction "1_1") (pintype "passive"))
      (node (ref "U6") (pin "14") (pinfunction "BIAS_14") (pintype "power_in"))
    )
    (net (code "49") (name "Net-(U6-BST)") (class "Default")
      (node (ref "C19") (pin "1") (pinfunction "1_1") (pintype "passive"))
      (node (ref "U6") (pin "12") (pinfunction "BST_12") (pintype "passive"))
    )
    (net (code "50") (name "Net-(U6-FB)") (class "Default")
      (node (ref "C76") (pin "1") (pinfunction "1_1") (pintype "passive"))
      (node (ref "R16") (pin "1") (pinfunction "1_1") (pintype "passive"))
      (node (ref "R18") (pin "2") (pinfunction "2_2") (pintype "passive"))
      (node (ref "U6") (pin "16") (pinfunction "FB_16") (pintype "input"))
    )
    (net (code "51") (name "Net-(U6-INTVCC)") (class "Default")
      (node (ref "C28") (pin "2") (pinfunction "2_2") (pintype "passive"))
      (node (ref "U6") (pin "13") (pinfunction "INTVCC_13") (pintype "power_in"))
    )
    (net (code "52") (name "Net-(U6-RT)") (class "Default")
      (node (ref "R21") (pin "2") (pinfunction "2_2") (pintype "passive"))
      (node (ref "U6") (pin "3") (pinfunction "RT_3") (pintype "passive"))
    )
    (net (code "53") (name "Net-(U6-SYNC)") (class "Default")
      (node (ref "R17") (pin "2") (pinfunction "2_2") (pintype "passive"))
      (node (ref "U6") (pin "1") (pinfunction "SYNC_1") (pintype "input"))
    )
    (net (code "54") (name "Net-(U6-TR{slash}SS)") (class "Default")
      (node (ref "C24") (pin "2") (pinfunction "2_2") (pintype "passive"))
      (node (ref "U6") (pin "2") (pinfunction "TR/SS_2") (pintype "input"))
    )
    (net (code "55") (name "Net-(U7-BST)") (class "Default")
      (node (ref "C30") (pin "1") (pinfunction "1_1") (pintype "passive"))
      (node (ref "U7") (pin "12") (pinfunction "BST_12") (pintype "passive"))
    )
    (net (code "56") (name "Net-(U7-FB)") (class "Default")
      (node (ref "C80") (pin "1") (pinfunction "1_1") (pintype "passive"))
      (node (ref "R28") (pin "1") (pinfunction "1_1") (pintype "passive"))
      (node (ref "R30") (pin "2") (pinfunction "2_2") (pintype "passive"))
      (node (ref "U7") (pin "16") (pinfunction "FB_16") (pintype "input"))
    )
    (net (code "57") (name "Net-(U7-INTVCC)") (class "Default")
      (node (ref "C32") (pin "2") (pinfunction "2_2") (pintype "passive"))
      (node (ref "U7") (pin "13") (pinfunction "INTVCC_13") (pintype "power_in"))
    )
    (net (code "58") (name "Net-(U7-RT)") (class "Default")
      (node (ref "R29") (pin "2") (pinfunction "2_2") (pintype "passive"))
      (node (ref "U7") (pin "3") (pinfunction "RT_3") (pintype "passive"))
    )
    (net (code "59") (name "Net-(U7-SYNC)") (class "Default")
      (node (ref "R25") (pin "2") (pinfunction "2_2") (pintype "passive"))
      (node (ref "U7") (pin "1") (pinfunction "SYNC_1") (pintype "input"))
    )
    (net (code "60") (name "Net-(U7-TR{slash}SS)") (class "Default")
      (node (ref "C31") (pin "2") (pinfunction "2_2") (pintype "passive"))
      (node (ref "U7") (pin "2") (pinfunction "TR/SS_2") (pintype "input"))
    )
    (net (code "61") (name "P1V2_CORE") (class "Default")
      (node (ref "IC5") (pin "5") (pinfunction "RS-_5") (pintype "passive"))
      (node (ref "L3") (pin "1") (pinfunction "1_1") (pintype "passive"))
      (node (ref "R20") (pin "2") (pinfunction "2_2") (pintype "passive"))
      (node (ref "R6") (pin "1") (pinfunction "1_1") (pintype "passive"))
    )
    (net (code "62") (name "P1V2_SERDES") (class "Default")
      (node (ref "L3") (pin "2") (pinfunction "2_2") (pintype "passive"))
    )
    (net (code "63") (name "P1V2_buck") (class "Default")
      (node (ref "C256") (pin "2") (pinfunction "2_2") (pintype "passive"))
      (node (ref "C257") (pin "2") (pinfunction "2_2") (pintype "passive"))
      (node (ref "C258") (pin "2") (pinfunction "2_2") (pintype "passive"))
      (node (ref "C259") (pin "2") (pinfunction "2_2") (pintype "passive"))
      (node (ref "C72") (pin "2") (pinfunction "2_2") (pintype "passive"))
      (node (ref "IC5") (pin "4") (pinfunction "RS+_4") (pintype "passive"))
      (node (ref "L1") (pin "2") (pinfunction "2_2") (pintype "passive"))
      (node (ref "R20") (pin "1") (pinfunction "1_1") (pintype "passive"))
      (node (ref "R4") (pin "2") (pinfunction "2_2") (pintype "passive"))
    )
    (net (code "64") (name "P1V8") (class "Default")
      (node (ref "IC6") (pin "5") (pinfunction "RS-_5") (pintype "passive"))
      (node (ref "R44") (pin "2") (pinfunction "2_2") (pintype "passive"))
    )
    (net (code "65") (name "P1V8_buck") (class "Default")
      (node (ref "C13") (pin "2") (pinfunction "2_2") (pintype "passive"))
      (node (ref "C14") (pin "2") (pinfunction "2_2") (pintype "passive"))
      (node (ref "C73") (pin "2") (pinfunction "2_2") (pintype "passive"))
      (node (ref "IC6") (pin "4") (pinfunction "RS+_4") (pintype "passive"))
      (node (ref "L2") (pin "2") (pinfunction "2_2") (pintype "passive"))
      (node (ref "R10") (pin "2") (pinfunction "2_2") (pintype "passive"))
      (node (ref "R44") (pin "1") (pinfunction "1_1") (pintype "passive"))
    )
    (net (code "66") (name "P2V5") (class "Default")
      (node (ref "IC8") (pin "5") (pinfunction "RS-_5") (pintype "passive"))
      (node (ref "L5") (pin "1") (pinfunction "1_1") (pintype "passive"))
      (node (ref "R15") (pin "2") (pinfunction "2_2") (pintype "passive"))
    )
    (net (code "67") (name "P2V5_Buck") (class "Default")
      (node (ref "C20") (pin "2") (pinfunction "2_2") (pintype "passive"))
      (node (ref "C21") (pin "2") (pinfunction "2_2") (pintype "passive"))
      (node (ref "C76") (pin "2") (pinfunction "2_2") (pintype "passive"))
      (node (ref "IC8") (pin "4") (pinfunction "RS+_4") (pintype "passive"))
      (node (ref "L4") (pin "2") (pinfunction "2_2") (pintype "passive"))
      (node (ref "R15") (pin "1") (pinfunction "1_1") (pintype "passive"))
      (node (ref "R16") (pin "2") (pinfunction "2_2") (pintype "passive"))
    )
    (net (code "68") (name "P2V5_PLL") (class "Default")
      (node (ref "L5") (pin "2") (pinfunction "2_2") (pintype "passive"))
    )
    (net (code "69") (name "P3V3") (class "Default")
      (node (ref "IC9") (pin "5") (pinfunction "RS-_5") (pintype "passive"))
      (node (ref "L7") (pin "1") (pinfunction "1_1") (pintype "passive"))
      (node (ref "R22") (pin "2") (pinfunction "2_2") (pintype "passive"))
    )
    (net (code "70") (name "P3V3_M") (class "Default")
      (node (ref "C10") (pin "2") (pinfunction "2_2") (pintype "passive"))
      (node (ref "C265") (pin "2") (pinfunction "2_2") (pintype "passive"))
      (node (ref "C269") (pin "2") (pinfunction "2_2") (pintype "passive"))
      (node (ref "C270") (pin "2") (pinfunction "2_2") (pintype "passive"))
      (node (ref "C74") (pin "2") (pinfunction "2_2") (pintype "passive"))
      (node (ref "IC4") (pin "3") (pinfunction "VCC_3") (pintype "passive"))
      (node (ref "IC5") (pin "3") (pinfunction "VCC_3") (pintype "passive"))
      (node (ref "IC6") (pin "3") (pinfunction "VCC_3") (pintype "passive"))
      (node (ref "IC8") (pin "3") (pinfunction "VCC_3") (pintype "passive"))
      (node (ref "IC9") (pin "3") (pinfunction "VCC_3") (pintype "passive"))
    )
    (net (code "71") (name "P3V3_PLL") (class "Default")
      (node (ref "L7") (pin "2") (pinfunction "2_2") (pintype "passive"))
    )
    (net (code "72") (name "P3V3_buck") (class "Default")
      (node (ref "C78") (pin "2") (pinfunction "2_2") (pintype "passive"))
      (node (ref "C79") (pin "2") (pinfunction "2_2") (pintype "passive"))
      (node (ref "C80") (pin "2") (pinfunction "2_2") (pintype "passive"))
      (node (ref "IC9") (pin "4") (pinfunction "RS+_4") (pintype "passive"))
      (node (ref "L6") (pin "2") (pinfunction "2_2") (pintype "passive"))
      (node (ref "R11") (pin "2") (pinfunction "2_2") (pintype "passive"))
      (node (ref "R19") (pin "2") (pinfunction "2_2") (pintype "passive"))
      (node (ref "R2") (pin "2") (pinfunction "2_2") (pintype "passive"))
      (node (ref "R22") (pin "1") (pinfunction "1_1") (pintype "passive"))
      (node (ref "R28") (pin "2") (pinfunction "2_2") (pintype "passive"))
      (node (ref "U7") (pin "14") (pinfunction "BIAS_14") (pintype "power_in"))
    )
    (net (code "73") (name "P12V0") (class "Default")
      (node (ref "C1") (pin "2") (pinfunction "2_2") (pintype "passive"))
      (node (ref "C11") (pin "2") (pinfunction "2_2") (pintype "passive"))
      (node (ref "C18") (pin "2") (pinfunction "2_2") (pintype "passive"))
      (node (ref "C29") (pin "2") (pinfunction "2_2") (pintype "passive"))
      (node (ref "C5") (pin "2") (pinfunction "2_2") (pintype "passive"))
      (node (ref "IC1") (pin "5") (pinfunction "VIN_5") (pintype "input"))
      (node (ref "IC1") (pin "6") (pinfunction "VIN_6") (pintype "input"))
      (node (ref "IC1") (pin "7") (pinfunction "VIN_7") (pintype "input"))
      (node (ref "IC4") (pin "4") (pinfunction "RS+_4") (pintype "passive"))
      (node (ref "R9") (pin "1") (pinfunction "1_1") (pintype "passive"))
      (node (ref "U3") (pin "5") (pinfunction "VIN_5") (pintype "power_in"))
      (node (ref "U3") (pin "6") (pinfunction "VIN_6") (pintype "power_in"))
      (node (ref "U6") (pin "5") (pinfunction "VIN_5") (pintype "power_in"))
      (node (ref "U6") (pin "6") (pinfunction "VIN_6") (pintype "power_in"))
      (node (ref "U7") (pin "5") (pinfunction "VIN_5") (pintype "power_in"))
      (node (ref "U7") (pin "6") (pinfunction "VIN_6") (pintype "power_in"))
    )
    (net (code "74") (name "unconnected-(IC1-NC-Pad25)") (class "Default")
      (node (ref "IC1") (pin "25") (pinfunction "NC_25") (pintype "passive"))
    )
    (net (code "75") (name "unconnected-(IC1-NC-Pad26)") (class "Default")
      (node (ref "IC1") (pin "26") (pinfunction "NC_26") (pintype "passive"))
    )
    (net (code "76") (name "unconnected-(IC1-NC-Pad27)") (class "Default")
      (node (ref "IC1") (pin "27") (pinfunction "NC_27") (pintype "passive"))
    )
    (net (code "77") (name "unconnected-(IC1-NC-Pad28)") (class "Default")
      (node (ref "IC1") (pin "28") (pinfunction "NC_28") (pintype "passive"))
    )
  )
)
